# Wireless_Battery_Charger.net
KiCad netlist of a schematic drawn in Altium Designer
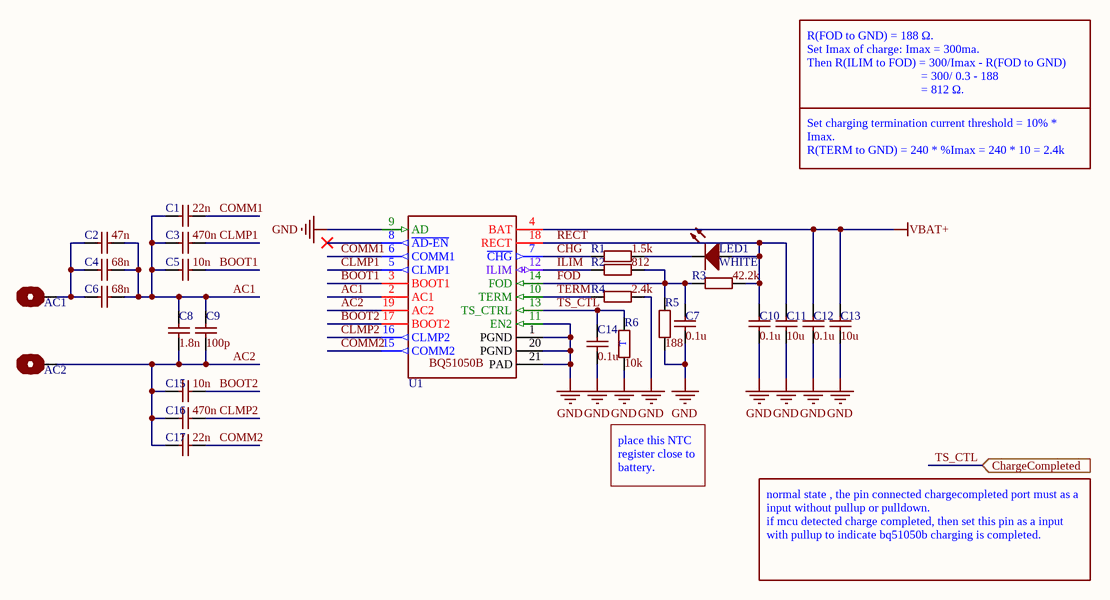
[diagram p0: Wireless Battery Charger.SchDoc]

(export (version "E")
  (design (tool "Eeschema 10.0.6"))
  (components
    (comp (ref "AC1")
      (value "Pad")
      (footprint "PAD")
      (description "PAD")
      (libsource (lib "接插器件封装库") (part "Pad"))
    )
    (comp (ref "AC2")
      (value "Pad")
      (footprint "PAD")
      (description "PAD")
      (libsource (lib "接插器件封装库") (part "Pad"))
    )
    (comp (ref "C1")
      (value "22n")
      (footprint "C0402_h")
      (description "Capacitor")
      (fields (field (name "PUBLISHER") "Altium Limited"))
      (libsource (lib "电子元件封装库") (part "贴片电容-无极性"))
    )
    (comp (ref "C2")
      (value "47n")
      (footprint "C0402_h")
      (description "Capacitor")
      (fields (field (name "PUBLISHER") "Altium Limited"))
      (libsource (lib "电子元件封装库") (part "贴片电容-无极性"))
    )
    (comp (ref "C3")
      (value "470n")
      (footprint "C0402_h")
      (description "Capacitor")
      (fields (field (name "PUBLISHER") "Altium Limited"))
      (libsource (lib "电子元件封装库") (part "贴片电容-无极性"))
    )
    (comp (ref "C4")
      (value "68n")
      (footprint "C0402_h")
      (description "Capacitor")
      (fields (field (name "PUBLISHER") "Altium Limited"))
      (libsource (lib "电子元件封装库") (part "贴片电容-无极性"))
    )
    (comp (ref "C5")
      (value "10n")
      (footprint "C0402_h")
      (description "Capacitor")
      (fields (field (name "PUBLISHER") "Altium Limited"))
      (libsource (lib "电子元件封装库") (part "贴片电容-无极性"))
    )
    (comp (ref "C6")
      (value "68n")
      (footprint "C0402_h")
      (description "Capacitor")
      (fields (field (name "PUBLISHER") "Altium Limited"))
      (libsource (lib "电子元件封装库") (part "贴片电容-无极性"))
    )
    (comp (ref "C7")
      (value "0.1u")
      (footprint "C0402_h")
      (description "Capacitor")
      (fields (field (name "PUBLISHER") "Altium Limited"))
      (libsource (lib "电子元件封装库") (part "贴片电容-无极性"))
    )
    (comp (ref "C8")
      (value "1.8n")
      (footprint "C0402_h")
      (description "Capacitor")
      (fields (field (name "PUBLISHER") "Altium Limited"))
      (libsource (lib "电子元件封装库") (part "贴片电容-无极性"))
    )
    (comp (ref "C9")
      (value "100p")
      (footprint "C0402_h")
      (description "Capacitor")
      (fields (field (name "PUBLISHER") "Altium Limited"))
      (libsource (lib "电子元件封装库") (part "贴片电容-无极性"))
    )
    (comp (ref "C10")
      (value "0.1u")
      (footprint "C0402_h")
      (description "Capacitor")
      (fields (field (name "PUBLISHER") "Altium Limited"))
      (libsource (lib "电子元件封装库") (part "贴片电容-无极性"))
    )
    (comp (ref "C11")
      (value "10u")
      (footprint "C0402_h")
      (description "Capacitor")
      (fields (field (name "PUBLISHER") "Altium Limited"))
      (libsource (lib "电子元件封装库") (part "贴片电容-无极性"))
    )
    (comp (ref "C12")
      (value "0.1u")
      (footprint "C0402_h")
      (description "Capacitor")
      (fields (field (name "PUBLISHER") "Altium Limited"))
      (libsource (lib "电子元件封装库") (part "贴片电容-无极性"))
    )
    (comp (ref "C13")
      (value "10u")
      (footprint "C0402_h")
      (description "Capacitor")
      (fields (field (name "PUBLISHER") "Altium Limited"))
      (libsource (lib "电子元件封装库") (part "贴片电容-无极性"))
    )
    (comp (ref "C14")
      (value "0.1u")
      (footprint "C0402_h")
      (description "Capacitor")
      (fields (field (name "PUBLISHER") "Altium Limited"))
      (libsource (lib "电子元件封装库") (part "贴片电容-无极性"))
    )
    (comp (ref "C15")
      (value "10n")
      (footprint "C0402_h")
      (description "Capacitor")
      (fields (field (name "PUBLISHER") "Altium Limited"))
      (libsource (lib "电子元件封装库") (part "贴片电容-无极性"))
    )
    (comp (ref "C16")
      (value "470n")
      (footprint "C0402_h")
      (description "Capacitor")
      (fields (field (name "PUBLISHER") "Altium Limited"))
      (libsource (lib "电子元件封装库") (part "贴片电容-无极性"))
    )
    (comp (ref "C17")
      (value "22n")
      (footprint "C0402_h")
      (description "Capacitor")
      (fields (field (name "PUBLISHER") "Altium Limited"))
      (libsource (lib "电子元件封装库") (part "贴片电容-无极性"))
    )
    (comp (ref "LED1")
      (value "LED")
      (footprint "LED0805")
      (description "led")
      (fields (field (name "COLOR") "WHITE") (field (name "PUBLISHER") "Altium Limited"))
      (libsource (lib "电子元件封装库") (part "LED"))
    )
    (comp (ref "R1")
      (value "1.5k")
      (footprint "R0402")
      (description "Register")
      (libsource (lib "") (part "贴片电阻_2"))
    )
    (comp (ref "R2")
      (value "812")
      (footprint "R0402")
      (description "Register")
      (libsource (lib "电子元件封装库") (part "贴片电阻"))
    )
    (comp (ref "R3")
      (value "42.2k")
      (footprint "R0402")
      (description "Register")
      (libsource (lib "电子元件封装库") (part "贴片电阻"))
    )
    (comp (ref "R4")
      (value "2.4k")
      (footprint "R0402")
      (description "Register")
      (libsource (lib "电子元件封装库") (part "贴片电阻"))
    )
    (comp (ref "R5")
      (value "188")
      (footprint "R0402")
      (description "Register")
      (libsource (lib "") (part "贴片电阻_1"))
    )
    (comp (ref "R6")
      (value "10k")
      (footprint "NTC")
      (description "Register")
      (libsource (lib "电子元件封装库") (part "热敏电阻"))
    )
    (comp (ref "U1")
      (value "BQ51050BRHLR")
      (footprint "VQFN-20")
      (description "4.2V Li-Ion Wireless Battery Charger, receiver")
      (fields (field (name "MANUFACTURER") "Texas Instruments"))
      (libsource (lib "电子元件封装库") (part "BQ51050BRHLR"))
    )
  )
  (nets
    (net (code "1") (name "/AC1") (class "Default")
      (node (ref "C1") (pin "1") (pinfunction "1_1") (pintype "passive"))
      (node (ref "C2") (pin "2") (pinfunction "2_2") (pintype "passive"))
      (node (ref "C3") (pin "1") (pinfunction "1_1") (pintype "passive"))
      (node (ref "C4") (pin "2") (pinfunction "2_2") (pintype "passive"))
      (node (ref "C5") (pin "1") (pinfunction "1_1") (pintype "passive"))
      (node (ref "C6") (pin "2") (pinfunction "2_2") (pintype "passive"))
      (node (ref "C8") (pin "2") (pinfunction "2_2") (pintype "passive"))
      (node (ref "C9") (pin "2") (pinfunction "2_2") (pintype "passive"))
      (node (ref "U1") (pin "2") (pinfunction "AC1_2") (pintype "power_in"))
    )
    (net (code "2") (name "/AC2") (class "Default")
      (node (ref "AC2") (pin "1") (pinfunction "1_1") (pintype "passive"))
      (node (ref "C15") (pin "1") (pinfunction "1_1") (pintype "passive"))
      (node (ref "C16") (pin "1") (pinfunction "1_1") (pintype "passive"))
      (node (ref "C17") (pin "1") (pinfunction "1_1") (pintype "passive"))
      (node (ref "C8") (pin "1") (pinfunction "1_1") (pintype "passive"))
      (node (ref "C9") (pin "1") (pinfunction "1_1") (pintype "passive"))
      (node (ref "U1") (pin "19") (pinfunction "AC2_19") (pintype "power_in"))
    )
    (net (code "3") (name "/BOOT1") (class "Default")
      (node (ref "C5") (pin "2") (pinfunction "2_2") (pintype "passive"))
      (node (ref "U1") (pin "3") (pinfunction "BOOT1_3") (pintype "power_in"))
    )
    (net (code "4") (name "/BOOT2") (class "Default")
      (node (ref "C15") (pin "2") (pinfunction "2_2") (pintype "passive"))
      (node (ref "U1") (pin "17") (pinfunction "BOOT2_17") (pintype "power_in"))
    )
    (net (code "5") (name "/CHG") (class "Default")
      (node (ref "R1") (pin "2") (pinfunction "2_2") (pintype "passive"))
      (node (ref "U1") (pin "7") (pinfunction "~{CHG}_7") (pintype "output"))
    )
    (net (code "6") (name "/CLMP1") (class "Default")
      (node (ref "C3") (pin "2") (pinfunction "2_2") (pintype "passive"))
      (node (ref "U1") (pin "5") (pinfunction "CLMP1_5") (pintype "output"))
    )
    (net (code "7") (name "/CLMP2") (class "Default")
      (node (ref "C16") (pin "2") (pinfunction "2_2") (pintype "passive"))
      (node (ref "U1") (pin "16") (pinfunction "CLMP2_16") (pintype "output"))
    )
    (net (code "8") (name "/COMM1") (class "Default")
      (node (ref "C1") (pin "2") (pinfunction "2_2") (pintype "passive"))
      (node (ref "U1") (pin "6") (pinfunction "COMM1_6") (pintype "output"))
    )
    (net (code "9") (name "/COMM2") (class "Default")
      (node (ref "C17") (pin "2") (pinfunction "2_2") (pintype "passive"))
      (node (ref "U1") (pin "15") (pinfunction "COMM2_15") (pintype "output"))
    )
    (net (code "10") (name "/FOD") (class "Default")
      (node (ref "C7") (pin "1") (pinfunction "1_1") (pintype "passive"))
      (node (ref "R2") (pin "2") (pinfunction "2_2") (pintype "passive"))
      (node (ref "R3") (pin "1") (pinfunction "1_1") (pintype "passive"))
      (node (ref "R5") (pin "1") (pinfunction "1_1") (pintype "passive"))
      (node (ref "U1") (pin "14") (pinfunction "FOD_14") (pintype "input"))
    )
    (net (code "11") (name "/ILIM") (class "Default")
      (node (ref "R2") (pin "1") (pinfunction "1_1") (pintype "passive"))
      (node (ref "U1") (pin "12") (pinfunction "ILIM_12") (pintype "bidirectional"))
    )
    (net (code "12") (name "/RECT") (class "Default")
      (node (ref "C10") (pin "2") (pinfunction "2_2") (pintype "passive"))
      (node (ref "C11") (pin "2") (pinfunction "2_2") (pintype "passive"))
      (node (ref "LED1") (pin "1") (pinfunction "A_1") (pintype "passive"))
      (node (ref "R3") (pin "2") (pinfunction "2_2") (pintype "passive"))
      (node (ref "U1") (pin "18") (pinfunction "RECT_18") (pintype "power_in"))
    )
    (net (code "13") (name "/TERM") (class "Default")
      (node (ref "R4") (pin "1") (pinfunction "1_1") (pintype "passive"))
      (node (ref "U1") (pin "10") (pinfunction "TERM_10") (pintype "input"))
    )
    (net (code "14") (name "/TS_CTL") (class "Default")
      (node (ref "C14") (pin "2") (pinfunction "2_2") (pintype "passive"))
      (node (ref "R6") (pin "2") (pinfunction "2_2") (pintype "passive"))
      (node (ref "U1") (pin "13") (pinfunction "TS_CTRL_13") (pintype "input"))
    )
    (net (code "15") (name "GND") (class "Default")
      (node (ref "C10") (pin "1") (pinfunction "1_1") (pintype "passive"))
      (node (ref "C11") (pin "1") (pinfunction "1_1") (pintype "passive"))
      (node (ref "C12") (pin "1") (pinfunction "1_1") (pintype "passive"))
      (node (ref "C13") (pin "1") (pinfunction "1_1") (pintype "passive"))
      (node (ref "C14") (pin "1") (pinfunction "1_1") (pintype "passive"))
      (node (ref "C7") (pin "2") (pinfunction "2_2") (pintype "passive"))
      (node (ref "R4") (pin "2") (pinfunction "2_2") (pintype "passive"))
      (node (ref "R5") (pin "2") (pinfunction "2_2") (pintype "passive"))
      (node (ref "R6") (pin "1") (pinfunction "1_1") (pintype "passive"))
      (node (ref "U1") (pin "1") (pinfunction "PGND_1") (pintype "power_in"))
      (node (ref "U1") (pin "11") (pinfunction "EN2_11") (pintype "input"))
      (node (ref "U1") (pin "20") (pinfunction "PGND_20") (pintype "power_in"))
      (node (ref "U1") (pin "21") (pinfunction "PAD_21") (pintype "passive"))
      (node (ref "U1") (pin "9") (pinfunction "AD_9") (pintype "input"))
    )
    (net (code "16") (name "Net-(AC1-Pad1)") (class "Default")
      (node (ref "AC1") (pin "1") (pinfunction "1_1") (pintype "passive"))
      (node (ref "C2") (pin "1") (pinfunction "1_1") (pintype "passive"))
      (node (ref "C4") (pin "1") (pinfunction "1_1") (pintype "passive"))
      (node (ref "C6") (pin "1") (pinfunction "1_1") (pintype "passive"))
    )
    (net (code "17") (name "Net-(LED1-K)") (class "Default")
      (node (ref "LED1") (pin "2") (pinfunction "K_2") (pintype "passive"))
      (node (ref "R1") (pin "1") (pinfunction "1_1") (pintype "passive"))
    )
    (net (code "18") (name "VBAT+") (class "Default")
      (node (ref "C12") (pin "2") (pinfunction "2_2") (pintype "passive"))
      (node (ref "C13") (pin "2") (pinfunction "2_2") (pintype "passive"))
      (node (ref "U1") (pin "4") (pinfunction "BAT_4") (pintype "power_in"))
    )
    (net (code "19") (name "unconnected-(U1-~{AD-EN}-Pad8)") (class "Default")
      (node (ref "U1") (pin "8") (pinfunction "~{AD-EN}_8") (pintype "output+no_connect"))
    )
  )
)
